# Webasto.net
KiCad netlist of a schematic drawn in EAGLE
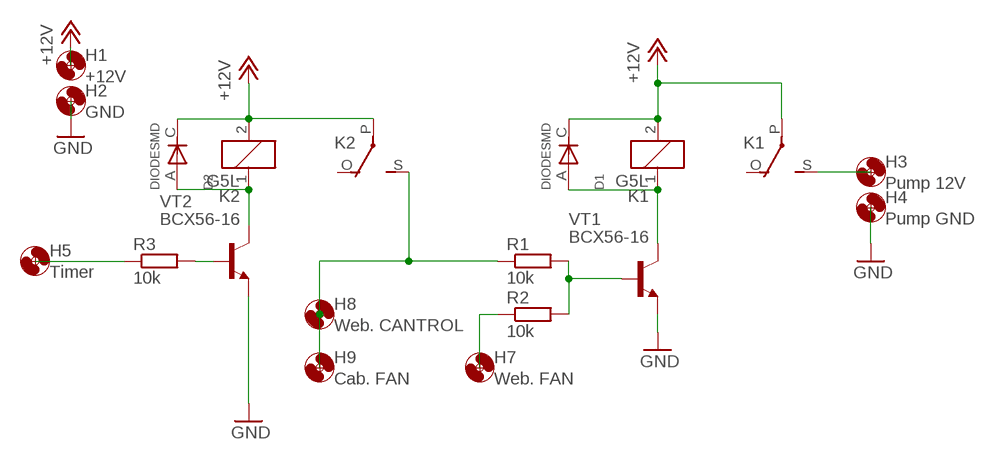
[diagram p0: schematic, sheet 1]

(export (version "E")
  (design (tool "Eeschema 10.0.6"))
  (components
    (comp (ref "D1")
      (value "DIODESMD")
      (footprint "eagle-import:DO214AC")
      (libsource (lib "eagle-import") (part "DIODESMD"))
    )
    (comp (ref "D2")
      (value "DIODESMD")
      (footprint "eagle-import:DO214AC")
      (libsource (lib "eagle-import") (part "DIODESMD"))
    )
    (comp (ref "H1")
      (value "+12V")
      (footprint "eagle-import:3,0")
      (libsource (lib "eagle-import") (part "MOUNT-HOLE3.0"))
    )
    (comp (ref "H2")
      (value "GND")
      (footprint "eagle-import:3,0")
      (libsource (lib "eagle-import") (part "MOUNT-HOLE3.0"))
    )
    (comp (ref "H3")
      (value "Pump 12V")
      (footprint "eagle-import:3,0")
      (libsource (lib "eagle-import") (part "MOUNT-HOLE3.0"))
    )
    (comp (ref "H4")
      (value "Pump GND")
      (footprint "eagle-import:3,0")
      (libsource (lib "eagle-import") (part "MOUNT-HOLE3.0"))
    )
    (comp (ref "H5")
      (value "Timer")
      (footprint "eagle-import:2,8")
      (libsource (lib "eagle-import") (part "MOUNT-HOLE2.8"))
    )
    (comp (ref "H7")
      (value "Web. FAN")
      (footprint "eagle-import:2,8")
      (libsource (lib "eagle-import") (part "MOUNT-HOLE2.8"))
    )
    (comp (ref "H8")
      (value "Web. CANTROL")
      (footprint "eagle-import:2,8")
      (libsource (lib "eagle-import") (part "MOUNT-HOLE2.8"))
    )
    (comp (ref "H9")
      (value "Cab. FAN")
      (footprint "eagle-import:2,8")
      (libsource (lib "eagle-import") (part "MOUNT-HOLE2.8"))
    )
    (comp (ref "K1")
      (value "G5L")
      (footprint "eagle-import:G5LE")
      (libsource (lib "eagle-import") (part "G5L"))
    )
    (comp (ref "K2")
      (value "G5L")
      (footprint "eagle-import:G5LE")
      (libsource (lib "eagle-import") (part "G5L"))
    )
    (comp (ref "R1")
      (value "10k")
      (footprint "eagle-import:R0805")
      (libsource (lib "eagle-import") (part "R-EU_R0805"))
    )
    (comp (ref "R2")
      (value "10k")
      (footprint "eagle-import:R0805")
      (libsource (lib "eagle-import") (part "R-EU_R0805"))
    )
    (comp (ref "R3")
      (value "10k")
      (footprint "eagle-import:R0805")
      (libsource (lib "eagle-import") (part "R-EU_R0805"))
    )
    (comp (ref "VT1")
      (value "BCX56-16")
      (footprint "eagle-import:SOT89-BCE")
      (libsource (lib "eagle-import") (part "BCX56-16"))
    )
    (comp (ref "VT2")
      (value "BCX56-16")
      (footprint "eagle-import:SOT89-BCE")
      (libsource (lib "eagle-import") (part "BCX56-16"))
    )
  )
  (nets
    (net (code "1") (name "+12V") (class "Default")
      (node (ref "D1") (pin "C") (pinfunction "KATOD_C") (pintype "power_in"))
      (node (ref "D2") (pin "C") (pinfunction "KATOD_C") (pintype "power_in"))
      (node (ref "H1") (pin "P$1") (pinfunction "P$1_P$1") (pintype "bidirectional"))
      (node (ref "K1") (pin "2") (pinfunction "2_2") (pintype "passive"))
      (node (ref "K1") (pin "P") (pinfunction "P_P") (pintype "passive"))
      (node (ref "K2") (pin "2") (pinfunction "2_2") (pintype "passive"))
      (node (ref "K2") (pin "P") (pinfunction "P_P") (pintype "passive"))
    )
    (net (code "2") (name "GND") (class "Default")
      (node (ref "H2") (pin "P$1") (pinfunction "P$1_P$1") (pintype "bidirectional"))
      (node (ref "H4") (pin "P$1") (pinfunction "P$1_P$1") (pintype "bidirectional"))
      (node (ref "VT1") (pin "E") (pinfunction "E_E") (pintype "passive"))
      (node (ref "VT2") (pin "E") (pinfunction "E_E") (pintype "passive"))
    )
    (net (code "3") (name "Net-(D1-ANOD)") (class "Default")
      (node (ref "D1") (pin "A") (pinfunction "ANOD_A") (pintype "power_in"))
      (node (ref "K1") (pin "1") (pinfunction "1_1") (pintype "passive"))
      (node (ref "VT1") (pin "C") (pinfunction "C_C") (pintype "passive"))
      (node (ref "VT1") (pin "C@1") (pinfunction "C_C@1") (pintype "passive"))
    )
    (net (code "4") (name "Net-(D2-ANOD)") (class "Default")
      (node (ref "D2") (pin "A") (pinfunction "ANOD_A") (pintype "power_in"))
      (node (ref "K2") (pin "1") (pinfunction "1_1") (pintype "passive"))
      (node (ref "VT2") (pin "C") (pinfunction "C_C") (pintype "passive"))
      (node (ref "VT2") (pin "C@1") (pinfunction "C_C@1") (pintype "passive"))
    )
    (net (code "5") (name "Net-(H3-PadP$1)") (class "Default")
      (node (ref "H3") (pin "P$1") (pinfunction "P$1_P$1") (pintype "bidirectional"))
      (node (ref "K1") (pin "S") (pinfunction "S_S") (pintype "passive"))
    )
    (net (code "6") (name "Net-(H5-PadP$1)") (class "Default")
      (node (ref "H5") (pin "P$1") (pinfunction "P$1_P$1") (pintype "bidirectional"))
      (node (ref "R3") (pin "1") (pinfunction "1_1") (pintype "passive"))
    )
    (net (code "7") (name "Net-(H7-PadP$1)") (class "Default")
      (node (ref "H7") (pin "P$1") (pinfunction "P$1_P$1") (pintype "bidirectional"))
      (node (ref "R2") (pin "1") (pinfunction "1_1") (pintype "passive"))
    )
    (net (code "8") (name "Net-(H8-PadP$1)") (class "Default")
      (node (ref "H8") (pin "P$1") (pinfunction "P$1_P$1") (pintype "bidirectional"))
      (node (ref "H9") (pin "P$1") (pinfunction "P$1_P$1") (pintype "bidirectional"))
      (node (ref "K2") (pin "S") (pinfunction "S_S") (pintype "passive"))
      (node (ref "R1") (pin "1") (pinfunction "1_1") (pintype "passive"))
    )
    (net (code "9") (name "Net-(R1-Pad2)") (class "Default")
      (node (ref "R1") (pin "2") (pinfunction "2_2") (pintype "passive"))
      (node (ref "R2") (pin "2") (pinfunction "2_2") (pintype "passive"))
      (node (ref "VT1") (pin "B") (pinfunction "B_B") (pintype "passive"))
    )
    (net (code "10") (name "Net-(R3-Pad2)") (class "Default")
      (node (ref "R3") (pin "2") (pinfunction "2_2") (pintype "passive"))
      (node (ref "VT2") (pin "B") (pinfunction "B_B") (pintype "passive"))
    )
    (net (code "11") (name "unconnected-(K1-PadO)") (class "Default")
      (node (ref "K1") (pin "O") (pinfunction "O_O") (pintype "passive"))
    )
    (net (code "12") (name "unconnected-(K2-PadO)") (class "Default")
      (node (ref "K2") (pin "O") (pinfunction "O_O") (pintype "passive"))
    )
  )
)
